# cpu.net
KiCad netlist of a schematic drawn in Altium Designer
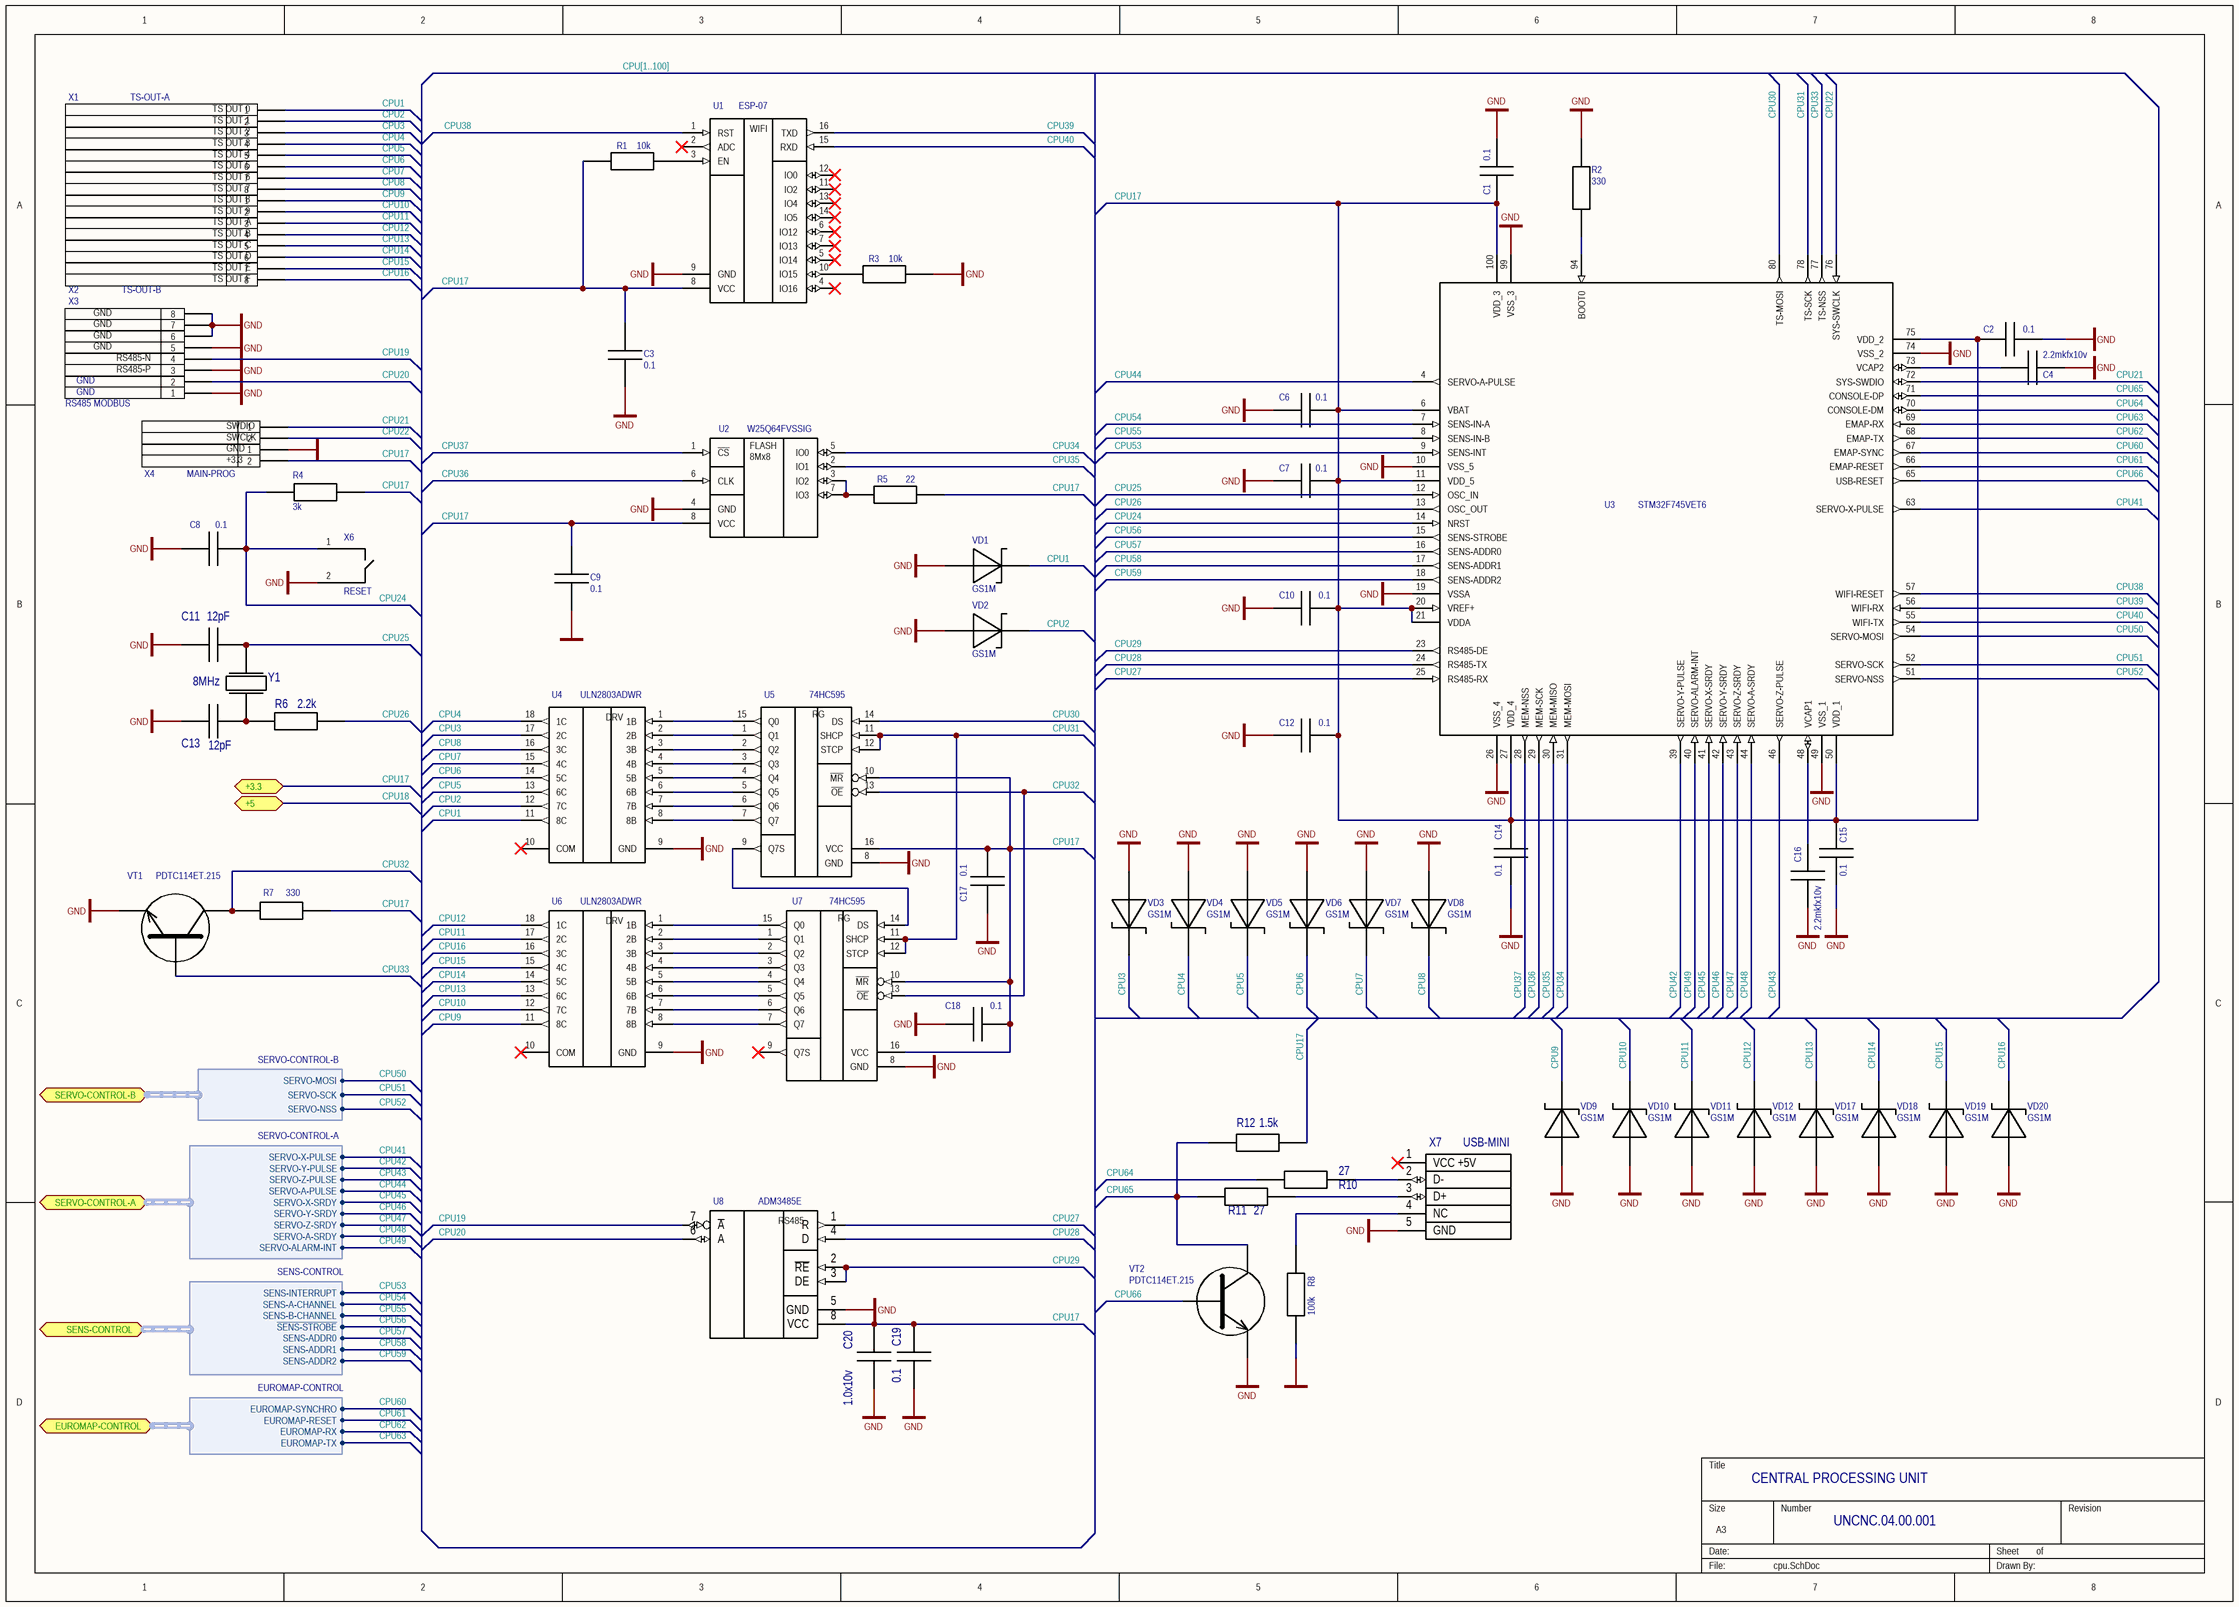
[diagram p0: cpu.SchDoc]

(export (version "E")
  (design (tool "Eeschema 10.0.6"))
  (components
    (comp (ref "C1")
      (value "0.1")
      (footprint "CAPC1608X05N")
      (description "SMD конденсатор")
      (libsource (lib "") (part "C_1"))
    )
    (comp (ref "C2")
      (value "0.1")
      (footprint "CAPC1608X05N")
      (description "SMD конденсатор")
      (libsource (lib "ulysses_library") (part "C"))
    )
    (comp (ref "C3")
      (value "0.1")
      (footprint "CAPC2012X04N")
      (description "SMD конденсатор")
      (libsource (lib "ulysses_library") (part "C"))
    )
    (comp (ref "C4")
      (value "2.2mkfx10v")
      (footprint "CAPC1608X05N")
      (description "SMD конденсатор")
      (libsource (lib "ulysses_library") (part "C"))
    )
    (comp (ref "C6")
      (value "0.1")
      (footprint "CAPC1608X05N")
      (description "SMD конденсатор")
      (libsource (lib "ulysses_library") (part "C"))
    )
    (comp (ref "C7")
      (value "0.1")
      (footprint "CAPC1608X05N")
      (description "SMD конденсатор")
      (libsource (lib "ulysses_library") (part "C"))
    )
    (comp (ref "C8")
      (value "0.1")
      (footprint "CAPC1608X05N")
      (description "SMD конденсатор")
      (libsource (lib "ulysses_library") (part "C"))
    )
    (comp (ref "C9")
      (value "0.1")
      (footprint "CAPC2012X04N")
      (description "SMD конденсатор")
      (libsource (lib "ulysses_library") (part "C"))
    )
    (comp (ref "C10")
      (value "0.1")
      (footprint "CAPC1608X05N")
      (description "SMD конденсатор")
      (libsource (lib "ulysses_library") (part "C"))
    )
    (comp (ref "C11")
      (value "12pF")
      (footprint "CAPC1608X05N")
      (description "SMD конденсатор")
      (libsource (lib "ulysses_library") (part "C"))
    )
    (comp (ref "C12")
      (value "0.1")
      (footprint "CAPC1608X05N")
      (description "SMD конденсатор")
      (libsource (lib "ulysses_library") (part "C"))
    )
    (comp (ref "C13")
      (value "12pF")
      (footprint "CAPC1608X05N")
      (description "SMD конденсатор")
      (libsource (lib "ulysses_library") (part "C"))
    )
    (comp (ref "C14")
      (value "0.1")
      (footprint "CAPC1608X05N")
      (description "SMD конденсатор")
      (libsource (lib "ulysses_library") (part "C"))
    )
    (comp (ref "C15")
      (value "0.1")
      (footprint "CAPC1608X05N")
      (description "SMD конденсатор")
      (libsource (lib "ulysses_library") (part "C"))
    )
    (comp (ref "C16")
      (value "2.2mkfx10v")
      (footprint "CAPC1608X05N")
      (description "SMD конденсатор")
      (libsource (lib "ulysses_library") (part "C"))
    )
    (comp (ref "C17")
      (value "0.1")
      (footprint "CAPC2012X04N")
      (description "SMD конденсатор")
      (libsource (lib "ulysses_library") (part "C"))
    )
    (comp (ref "C18")
      (value "0.1")
      (footprint "CAPC2012X04N")
      (description "SMD конденсатор")
      (libsource (lib "ulysses_library") (part "C"))
    )
    (comp (ref "C19")
      (value "0.1")
      (footprint "CAPC2012X04N")
      (description "SMD конденсатор")
      (libsource (lib "ulysses_library") (part "C"))
    )
    (comp (ref "C20")
      (value "1.0x10v")
      (footprint "CAPC2012X04N")
      (description "SMD конденсатор")
      (libsource (lib "ulysses_library") (part "C"))
    )
    (comp (ref "R1")
      (value "10k")
      (footprint "RESC2012X04N")
      (description "SMD резистор")
      (libsource (lib "ulysses_library") (part "R"))
    )
    (comp (ref "R2")
      (value "330")
      (footprint "RESC1608X05N")
      (description "SMD резистор")
      (libsource (lib "") (part "R_1"))
    )
    (comp (ref "R3")
      (value "10k")
      (footprint "RESC2012X04N")
      (description "SMD резистор")
      (libsource (lib "ulysses_library") (part "R"))
    )
    (comp (ref "R4")
      (value "3k")
      (footprint "RESC1608X05N")
      (description "SMD резистор")
      (libsource (lib "ulysses_library") (part "R"))
    )
    (comp (ref "R5")
      (value "22")
      (footprint "RESC2012X04N")
      (description "SMD резистор")
      (libsource (lib "ulysses_library") (part "R"))
    )
    (comp (ref "R6")
      (value "2.2k")
      (footprint "RESC1608X05N")
      (description "SMD резистор")
      (libsource (lib "ulysses_library") (part "R"))
    )
    (comp (ref "R7")
      (value "330")
      (footprint "RESC1608X05N")
      (description "SMD резистор")
      (libsource (lib "ulysses_library") (part "R"))
    )
    (comp (ref "R8")
      (value "100k")
      (footprint "RESC2012X04N")
      (description "SMD резистор")
      (libsource (lib "ulysses_library") (part "R"))
    )
    (comp (ref "R10")
      (value "27")
      (footprint "RESC2012X04N")
      (description "SMD резистор")
      (libsource (lib "ulysses_library") (part "R"))
    )
    (comp (ref "R11")
      (value "27")
      (footprint "RESC2012X04N")
      (description "SMD резистор")
      (libsource (lib "ulysses_library") (part "R"))
    )
    (comp (ref "R12")
      (value "1.5k")
      (footprint "RESC2012X04N")
      (description "SMD резистор")
      (libsource (lib "ulysses_library") (part "R"))
    )
    (comp (ref "U1")
      (value "ESP-07")
      (footprint "ESP-07")
      (description "WIFI модуль")
      (libsource (lib "ulysses_library") (part "ESP-07 Wi-Fi module"))
    )
    (comp (ref "U2")
      (value "W25Q64FVSSIG")
      (footprint "SOIC127P790X203-8N(WIDE)")
      (description "FLASH 8Mx8")
      (libsource (lib "ulysses_library") (part "W25Q64FVSSIG"))
    )
    (comp (ref "U3")
      (value "STM32F745VET6")
      (footprint "TSQFP50P1600X1600X160-100N")
      (description "ARM7 microcontroller")
      (libsource (lib "ulysses_library") (part "STM32F745VET6"))
    )
    (comp (ref "U4")
      (value "ULN2803ADWR")
      (footprint "SOIC127P1030X265-18N")
      (description "8 Darlington transistors")
      (libsource (lib "ulysses_library") (part "ULN2803ADWR"))
    )
    (comp (ref "U5")
      (value "74HC595")
      (footprint "SOP127P700X210-16N")
      (libsource (lib "ulysses_library") (part "74HC595"))
    )
    (comp (ref "U6")
      (value "ULN2803ADWR")
      (footprint "SOIC127P1030X265-18N")
      (description "8 Darlington transistors")
      (libsource (lib "ulysses_library") (part "ULN2803ADWR"))
    )
    (comp (ref "U7")
      (value "74HC595")
      (footprint "SOP127P700X210-16N")
      (libsource (lib "ulysses_library") (part "74HC595"))
    )
    (comp (ref "U8")
      (value "ADM3485E")
      (footprint "SOIC127P600X175-8N")
      (description "RS-485 line driver")
      (libsource (lib "ulysses_library") (part "SN65176BD"))
    )
    (comp (ref "VD1")
      (value "GS1M")
      (footprint "DIOM4336X21N")
      (description "диод Шоттки")
      (libsource (lib "ulysses_library") (part "SS26"))
    )
    (comp (ref "VD2")
      (value "GS1M")
      (footprint "DIOM4336X21N")
      (description "диод Шоттки")
      (libsource (lib "ulysses_library") (part "SS26"))
    )
    (comp (ref "VD3")
      (value "GS1M")
      (footprint "DIOM4336X21N")
      (description "диод Шоттки")
      (libsource (lib "ulysses_library") (part "SS26"))
    )
    (comp (ref "VD4")
      (value "GS1M")
      (footprint "DIOM4336X21N")
      (description "диод Шоттки")
      (libsource (lib "ulysses_library") (part "SS26"))
    )
    (comp (ref "VD5")
      (value "GS1M")
      (footprint "DIOM4336X21N")
      (description "диод Шоттки")
      (libsource (lib "ulysses_library") (part "SS26"))
    )
    (comp (ref "VD6")
      (value "GS1M")
      (footprint "DIOM4336X21N")
      (description "диод Шоттки")
      (libsource (lib "ulysses_library") (part "SS26"))
    )
    (comp (ref "VD7")
      (value "GS1M")
      (footprint "DIOM4336X21N")
      (description "диод Шоттки")
      (libsource (lib "ulysses_library") (part "SS26"))
    )
    (comp (ref "VD8")
      (value "GS1M")
      (footprint "DIOM4336X21N")
      (description "диод Шоттки")
      (libsource (lib "") (part "SS26_1"))
    )
    (comp (ref "VD9")
      (value "GS1M")
      (footprint "DIOM4336X21N")
      (description "диод Шоттки")
      (libsource (lib "ulysses_library") (part "SS26"))
    )
    (comp (ref "VD10")
      (value "GS1M")
      (footprint "DIOM4336X21N")
      (description "диод Шоттки")
      (libsource (lib "ulysses_library") (part "SS26"))
    )
    (comp (ref "VD11")
      (value "GS1M")
      (footprint "DIOM4336X21N")
      (description "диод Шоттки")
      (libsource (lib "ulysses_library") (part "SS26"))
    )
    (comp (ref "VD12")
      (value "GS1M")
      (footprint "DIOM4336X21N")
      (description "диод Шоттки")
      (libsource (lib "ulysses_library") (part "SS26"))
    )
    (comp (ref "VD17")
      (value "GS1M")
      (footprint "DIOM4336X21N")
      (description "диод Шоттки")
      (libsource (lib "ulysses_library") (part "SS26"))
    )
    (comp (ref "VD18")
      (value "GS1M")
      (footprint "DIOM4336X21N")
      (description "диод Шоттки")
      (libsource (lib "ulysses_library") (part "SS26"))
    )
    (comp (ref "VD19")
      (value "GS1M")
      (footprint "DIOM4336X21N")
      (description "диод Шоттки")
      (libsource (lib "ulysses_library") (part "SS26"))
    )
    (comp (ref "VD20")
      (value "GS1M")
      (footprint "DIOM4336X21N")
      (description "диод Шоттки")
      (libsource (lib "ulysses_library") (part "SS26"))
    )
    (comp (ref "VT1")
      (value "PDTC114ET.215")
      (footprint "SOT95P238X102-3N")
      (description "NPN transistor with bias circuit")
      (libsource (lib "ulysses_library") (part "PDTC114ET.215"))
    )
    (comp (ref "VT2")
      (value "PDTC114ET.215")
      (footprint "SOT95P238X102-3N")
      (description "NPN transistor with bias circuit")
      (libsource (lib "") (part "PDTC114ET.215_1"))
    )
    (comp (ref "X1")
      (value "TS-OUT-A")
      (footprint "MINI-FIT-8-WAY-SM")
      (libsource (lib "ulysses_library") (part "MINI-FIT-8-WAY-M"))
    )
    (comp (ref "X2")
      (value "TS-OUT-B")
      (footprint "MINI-FIT-8-WAY-SM")
      (libsource (lib "") (part "MINI-FIT-8-WAY-M_1"))
    )
    (comp (ref "X3")
      (value "RS485 MODBUS")
      (footprint "RJ45-CAN")
      (description "CAN-Bus connector")
      (libsource (lib "ulysses_library") (part "RJ45-CAN"))
    )
    (comp (ref "X4")
      (value "MAIN-PROG")
      (footprint "ZL201-2")
      (libsource (lib "ulysses_library") (part "Jamper ZL201"))
    )
    (comp (ref "X5")
      (value "Jamper ZL201")
      (footprint "ZL201-2")
      (libsource (lib "ulysses_library") (part "Jamper ZL201"))
    )
    (comp (ref "X6")
      (value "RESET")
      (footprint "TACT SWITCH")
      (libsource (lib "ulysses_library") (part "TACT SWITCH"))
    )
    (comp (ref "X7")
      (value "USB-MINI")
      (footprint "229-5FB-MINI-USB")
      (description "Разъем USB-B розетка")
      (libsource (lib "ulysses_library") (part "USB-MINI"))
    )
    (comp (ref "Y1")
      (value "8MHz")
      (footprint "KX-13")
      (description "Кварцевый резонатор")
      (libsource (lib "ulysses_library") (part "CERAMIC-RESONATOR"))
    )
  )
  (nets
    (net (code "40") (name "/CPU1") (class "Default")
      (node (ref "U4") (pin "11") (pinfunction "8C_11") (pintype "output"))
      (node (ref "VD1") (pin "1") (pinfunction "C_1") (pintype "passive"))
      (node (ref "X1") (pin "1") (pinfunction "1_1") (pintype "passive"))
    )
    (net (code "41") (name "/CPU2") (class "Default")
      (node (ref "U4") (pin "12") (pinfunction "7C_12") (pintype "output"))
      (node (ref "VD2") (pin "1") (pinfunction "C_1") (pintype "passive"))
      (node (ref "X1") (pin "2") (pinfunction "2_2") (pintype "passive"))
    )
    (net (code "42") (name "/CPU3") (class "Default")
      (node (ref "U4") (pin "17") (pinfunction "2C_17") (pintype "output"))
      (node (ref "VD3") (pin "1") (pinfunction "C_1") (pintype "passive"))
      (node (ref "X1") (pin "3") (pinfunction "3_3") (pintype "passive"))
    )
    (net (code "43") (name "/CPU4") (class "Default")
      (node (ref "U4") (pin "18") (pinfunction "1C_18") (pintype "output"))
      (node (ref "VD4") (pin "1") (pinfunction "C_1") (pintype "passive"))
      (node (ref "X1") (pin "4") (pinfunction "4_4") (pintype "passive"))
    )
    (net (code "44") (name "/CPU5") (class "Default")
      (node (ref "U4") (pin "13") (pinfunction "6C_13") (pintype "output"))
      (node (ref "VD5") (pin "1") (pinfunction "C_1") (pintype "passive"))
      (node (ref "X1") (pin "5") (pinfunction "5_5") (pintype "passive"))
    )
    (net (code "45") (name "/CPU6") (class "Default")
      (node (ref "U4") (pin "14") (pinfunction "5C_14") (pintype "output"))
      (node (ref "VD6") (pin "1") (pinfunction "C_1") (pintype "passive"))
      (node (ref "X1") (pin "6") (pinfunction "6_6") (pintype "passive"))
    )
    (net (code "46") (name "/CPU7") (class "Default")
      (node (ref "U4") (pin "15") (pinfunction "4C_15") (pintype "output"))
      (node (ref "VD7") (pin "1") (pinfunction "C_1") (pintype "passive"))
      (node (ref "X1") (pin "7") (pinfunction "7_7") (pintype "passive"))
    )
    (net (code "47") (name "/CPU8") (class "Default")
      (node (ref "U4") (pin "16") (pinfunction "3C_16") (pintype "output"))
      (node (ref "VD8") (pin "1") (pinfunction "C_1") (pintype "passive"))
      (node (ref "X1") (pin "8") (pinfunction "8_8") (pintype "passive"))
    )
    (net (code "48") (name "/CPU9") (class "Default")
      (node (ref "U6") (pin "11") (pinfunction "8C_11") (pintype "output"))
      (node (ref "VD9") (pin "1") (pinfunction "C_1") (pintype "passive"))
      (node (ref "X2") (pin "1") (pinfunction "1_1") (pintype "passive"))
    )
    (net (code "49") (name "/CPU10") (class "Default")
      (node (ref "U6") (pin "12") (pinfunction "7C_12") (pintype "output"))
      (node (ref "VD10") (pin "1") (pinfunction "C_1") (pintype "passive"))
      (node (ref "X2") (pin "2") (pinfunction "2_2") (pintype "passive"))
    )
    (net (code "50") (name "/CPU11") (class "Default")
      (node (ref "U6") (pin "17") (pinfunction "2C_17") (pintype "output"))
      (node (ref "VD11") (pin "1") (pinfunction "C_1") (pintype "passive"))
      (node (ref "X2") (pin "3") (pinfunction "3_3") (pintype "passive"))
    )
    (net (code "51") (name "/CPU12") (class "Default")
      (node (ref "U6") (pin "18") (pinfunction "1C_18") (pintype "output"))
      (node (ref "VD12") (pin "1") (pinfunction "C_1") (pintype "passive"))
      (node (ref "X2") (pin "4") (pinfunction "4_4") (pintype "passive"))
    )
    (net (code "52") (name "/CPU13") (class "Default")
      (node (ref "U6") (pin "13") (pinfunction "6C_13") (pintype "output"))
      (node (ref "VD17") (pin "1") (pinfunction "C_1") (pintype "passive"))
      (node (ref "X2") (pin "5") (pinfunction "5_5") (pintype "passive"))
    )
    (net (code "53") (name "/CPU14") (class "Default")
      (node (ref "U6") (pin "14") (pinfunction "5C_14") (pintype "output"))
      (node (ref "VD18") (pin "1") (pinfunction "C_1") (pintype "passive"))
      (node (ref "X2") (pin "6") (pinfunction "6_6") (pintype "passive"))
    )
    (net (code "54") (name "/CPU15") (class "Default")
      (node (ref "U6") (pin "15") (pinfunction "4C_15") (pintype "output"))
      (node (ref "VD19") (pin "1") (pinfunction "C_1") (pintype "passive"))
      (node (ref "X2") (pin "7") (pinfunction "7_7") (pintype "passive"))
    )
    (net (code "55") (name "/CPU16") (class "Default")
      (node (ref "U6") (pin "16") (pinfunction "3C_16") (pintype "output"))
      (node (ref "VD20") (pin "1") (pinfunction "C_1") (pintype "passive"))
      (node (ref "X2") (pin "8") (pinfunction "8_8") (pintype "passive"))
    )
    (net (code "56") (name "/CPU17") (class "Default")
      (node (ref "C1") (pin "1") (pinfunction "1_1") (pintype "passive"))
      (node (ref "C10") (pin "1") (pinfunction "1_1") (pintype "passive"))
      (node (ref "C12") (pin "1") (pinfunction "1_1") (pintype "passive"))
      (node (ref "C14") (pin "2") (pinfunction "2_2") (pintype "passive"))
      (node (ref "C15") (pin "2") (pinfunction "2_2") (pintype "passive"))
      (node (ref "C17") (pin "2") (pinfunction "2_2") (pintype "passive"))
      (node (ref "C18") (pin "2") (pinfunction "2_2") (pintype "passive"))
      (node (ref "C19") (pin "2") (pinfunction "2_2") (pintype "passive"))
      (node (ref "C2") (pin "2") (pinfunction "2_2") (pintype "passive"))
      (node (ref "C20") (pin "2") (pinfunction "2_2") (pintype "passive"))
      (node (ref "C3") (pin "2") (pinfunction "2_2") (pintype "passive"))
      (node (ref "C6") (pin "1") (pinfunction "1_1") (pintype "passive"))
      (node (ref "C7") (pin "1") (pinfunction "1_1") (pintype "passive"))
      (node (ref "C9") (pin "2") (pinfunction "2_2") (pintype "passive"))
      (node (ref "R1") (pin "1") (pintype "passive"))
      (node (ref "R12") (pin "2") (pinfunction "2_2") (pintype "passive"))
      (node (ref "R4") (pin "1") (pintype "passive"))
      (node (ref "R5") (pin "2") (pinfunction "2_2") (pintype "passive"))
      (node (ref "R7") (pin "1") (pintype "passive"))
      (node (ref "U1") (pin "8") (pinfunction "VCC_8") (pintype "power_in"))
      (node (ref "U2") (pin "8") (pinfunction "VCC_8") (pintype "power_in"))
      (node (ref "U3") (pin "100") (pinfunction "VDD_3_100") (pintype "power_in"))
      (node (ref "U3") (pin "11") (pinfunction "VDD_5_11") (pintype "power_in"))
      (node (ref "U3") (pin "20") (pinfunction "VREF+_20") (pintype "input"))
      (node (ref "U3") (pin "21") (pinfunction "VDDA_21") (pintype "power_in"))
      (node (ref "U3") (pin "27") (pinfunction "VDD_4_27") (pintype "power_in"))
      (node (ref "U3") (pin "50") (pinfunction "VDD_1_50") (pintype "power_in"))
      (node (ref "U3") (pin "6") (pinfunction "VBAT_6") (pintype "power_in"))
      (node (ref "U3") (pin "75") (pinfunction "VDD_2_75") (pintype "power_in"))
      (node (ref "U5") (pin "10") (pinfunction "~{MR}_10") (pintype "input"))
      (node (ref "U5") (pin "16") (pinfunction "VCC_16") (pintype "power_in"))
      (node (ref "U7") (pin "10") (pinfunction "~{MR}_10") (pintype "input"))
      (node (ref "U7") (pin "16") (pinfunction "VCC_16") (pintype "power_in"))
      (node (ref "U8") (pin "8") (pinfunction "VCC_8") (pintype "power_in"))
      (node (ref "X5") (pin "2") (pinfunction "2_2") (pintype "passive"))
    )
    (net (code "58") (name "/CPU19") (class "Default")
      (node (ref "U8") (pin "7") (pinfunction "~{A}_7") (pintype "bidirectional"))
      (node (ref "X3") (pin "4") (pinfunction "4_4") (pintype "passive"))
    )
    (net (code "59") (name "/CPU20") (class "Default")
      (node (ref "U8") (pin "6") (pinfunction "A_6") (pintype "bidirectional"))
      (node (ref "X3") (pin "2") (pinfunction "2_2") (pintype "passive"))
    )
    (net (code "60") (name "/CPU21") (class "Default")
      (node (ref "U3") (pin "72") (pinfunction "SYS-SWDIO_72") (pintype "bidirectional"))
      (node (ref "X4") (pin "1") (pinfunction "1_1") (pintype "passive"))
    )
    (net (code "61") (name "/CPU22") (class "Default")
      (node (ref "U3") (pin "76") (pinfunction "SYS-SWCLK_76") (pintype "input"))
      (node (ref "X4") (pin "2") (pinfunction "2_2") (pintype "passive"))
    )
    (net (code "62") (name "/CPU24") (class "Default")
      (node (ref "C8") (pin "1") (pinfunction "1_1") (pintype "passive"))
      (node (ref "R4") (pin "2") (pinfunction "2_2") (pintype "passive"))
      (node (ref "U3") (pin "14") (pinfunction "NRST_14") (pintype "input"))
      (node (ref "X6") (pin "1") (pinfunction "1_1") (pintype "passive"))
    )
    (net (code "63") (name "/CPU25") (class "Default")
      (node (ref "C11") (pin "2") (pinfunction "2_2") (pintype "passive"))
      (node (ref "U3") (pin "12") (pinfunction "OSC_IN_12") (pintype "input"))
      (node (ref "Y1") (pin "2") (pinfunction "2_2") (pintype "passive"))
    )
    (net (code "64") (name "/CPU26") (class "Default")
      (node (ref "R6") (pin "2") (pinfunction "2_2") (pintype "passive"))
      (node (ref "U3") (pin "13") (pinfunction "OSC_OUT_13") (pintype "output"))
    )
    (net (code "65") (name "/CPU27") (class "Default")
      (node (ref "U3") (pin "25") (pinfunction "RS485-RX_25") (pintype "input"))
      (node (ref "U8") (pin "1") (pinfunction "R_1") (pintype "output"))
    )
    (net (code "66") (name "/CPU28") (class "Default")
      (node (ref "U3") (pin "24") (pinfunction "RS485-TX_24") (pintype "output"))
      (node (ref "U8") (pin "4") (pinfunction "D_4") (pintype "input"))
    )
    (net (code "67") (name "/CPU29") (class "Default")
      (node (ref "U3") (pin "23") (pinfunction "RS485-DE_23") (pintype "output"))
      (node (ref "U8") (pin "2") (pinfunction "~{RE}_2") (pintype "input"))
      (node (ref "U8") (pin "3") (pinfunction "DE_3") (pintype "input"))
    )
    (net (code "68") (name "/CPU30") (class "Default")
      (node (ref "U3") (pin "80") (pinfunction "TS-MOSI_80") (pintype "output"))
      (node (ref "U5") (pin "14") (pinfunction "DS_14") (pintype "input"))
    )
    (net (code "69") (name "/CPU31") (class "Default")
      (node (ref "U3") (pin "78") (pinfunction "TS-SCK_78") (pintype "output"))
      (node (ref "U5") (pin "11") (pinfunction "SHCP_11") (pintype "input"))
      (node (ref "U5") (pin "12") (pinfunction "STCP_12") (pintype "input"))
      (node (ref "U7") (pin "11") (pinfunction "SHCP_11") (pintype "input"))
      (node (ref "U7") (pin "12") (pinfunction "STCP_12") (pintype "input"))
    )
    (net (code "70") (name "/CPU32") (class "Default")
      (node (ref "R7") (pin "2") (pinfunction "2_2") (pintype "passive"))
      (node (ref "U5") (pin "13") (pinfunction "~{OE}_13") (pintype "input"))
      (node (ref "U7") (pin "13") (pinfunction "~{OE}_13") (pintype "input"))
      (node (ref "VT1") (pin "3") (pinfunction "C_3") (pintype "power_in"))
    )
    (net (code "71") (name "/CPU33") (class "Default")
      (node (ref "U3") (pin "77") (pinfunction "TS-NSS_77") (pintype "output"))
      (node (ref "VT1") (pin "1") (pinfunction "B_1") (pintype "power_in"))
    )
    (net (code "72") (name "/CPU34") (class "Default")
      (node (ref "U2") (pin "5") (pinfunction "IO0_5") (pintype "bidirectional"))
      (node (ref "U3") (pin "31") (pinfunction "MEM-MOSI_31") (pintype "output"))
    )
    (net (code "73") (name "/CPU35") (class "Default")
      (node (ref "U2") (pin "2") (pinfunction "IO1_2") (pintype "bidirectional"))
      (node (ref "U3") (pin "30") (pinfunction "MEM-MISO_30") (pintype "input"))
    )
    (net (code "74") (name "/CPU36") (class "Default")
      (node (ref "U2") (pin "6") (pinfunction "CLK_6") (pintype "input"))
      (node (ref "U3") (pin "29") (pinfunction "MEM-SCK_29") (pintype "output"))
    )
    (net (code "75") (name "/CPU37") (class "Default")
      (node (ref "U2") (pin "1") (pinfunction "~{CS}_1") (pintype "input"))
      (node (ref "U3") (pin "28") (pinfunction "MEM-NSS_28") (pintype "output"))
    )
    (net (code "76") (name "/CPU38") (class "Default")
      (node (ref "U1") (pin "1") (pinfunction "RST_1") (pintype "input"))
      (node (ref "U3") (pin "57") (pinfunction "WIFI-RESET_57") (pintype "output"))
    )
    (net (code "77") (name "/CPU39") (class "Default")
      (node (ref "U1") (pin "16") (pinfunction "TXD_16") (pintype "output"))
      (node (ref "U3") (pin "56") (pinfunction "WIFI-RX_56") (pintype "input"))
    )
    (net (code "78") (name "/CPU40") (class "Default")
      (node (ref "U1") (pin "15") (pinfunction "RXD_15") (pintype "input"))
      (node (ref "U3") (pin "55") (pinfunction "WIFI-TX_55") (pintype "output"))
    )
    (net (code "79") (name "/CPU41") (class "Default")
      (node (ref "U3") (pin "63") (pinfunction "SERVO-X-PULSE_63") (pintype "output"))
    )
    (net (code "80") (name "/CPU42") (class "Default")
      (node (ref "U3") (pin "39") (pinfunction "SERVO-Y-PULSE_39") (pintype "output"))
    )
    (net (code "81") (name "/CPU43") (class "Default")
      (node (ref "U3") (pin "46") (pinfunction "SERVO-Z-PULSE_46") (pintype "output"))
    )
    (net (code "82") (name "/CPU44") (class "Default")
      (node (ref "U3") (pin "4") (pinfunction "SERVO-A-PULSE_4") (pintype "output"))
    )
    (net (code "83") (name "/CPU45") (class "Default")
      (node (ref "U3") (pin "41") (pinfunction "SERVO-X-SRDY_41") (pintype "input"))
    )
    (net (code "84") (name "/CPU46") (class "Default")
      (node (ref "U3") (pin "42") (pinfunction "SERVO-Y-SRDY_42") (pintype "input"))
    )
    (net (code "85") (name "/CPU47") (class "Default")
      (node (ref "U3") (pin "43") (pinfunction "SERVO-Z-SRDY_43") (pintype "input"))
    )
    (net (code "86") (name "/CPU48") (class "Default")
      (node (ref "U3") (pin "44") (pinfunction "SERVO-A-SRDY_44") (pintype "input"))
    )
    (net (code "87") (name "/CPU49") (class "Default")
      (node (ref "U3") (pin "40") (pinfunction "SERVO-ALARM-INT_40") (pintype "input"))
    )
    (net (code "88") (name "/CPU50") (class "Default")
      (node (ref "U3") (pin "54") (pinfunction "SERVO-MOSI_54") (pintype "output"))
    )
    (net (code "89") (name "/CPU51") (class "Default")
      (node (ref "U3") (pin "52") (pinfunction "SERVO-SCK_52") (pintype "output"))
    )
    (net (code "90") (name "/CPU52") (class "Default")
      (node (ref "U3") (pin "51") (pinfunction "SERVO-NSS_51") (pintype "output"))
    )
    (net (code "91") (name "/CPU53") (class "Default")
      (node (ref "U3") (pin "9") (pinfunction "SENS-INT_9") (pintype "input"))
    )
    (net (code "92") (name "/CPU54") (class "Default")
      (node (ref "U3") (pin "7") (pinfunction "SENS-IN-A_7") (pintype "input"))
    )
    (net (code "93") (name "/CPU55") (class "Default")
      (node (ref "U3") (pin "8") (pinfunction "SENS-IN-B_8") (pintype "input"))
    )
    (net (code "94") (name "/CPU56") (class "Default")
      (node (ref "U3") (pin "15") (pinfunction "SENS-STROBE_15") (pintype "output"))
    )
    (net (code "95") (name "/CPU57") (class "Default")
      (node (ref "U3") (pin "16") (pinfunction "SENS-ADDR0_16") (pintype "output"))
    )
    (net (code "96") (name "/CPU58") (class "Default")
      (node (ref "U3") (pin "17") (pinfunction "SENS-ADDR1_17") (pintype "output"))
    )
    (net (code "97") (name "/CPU59") (class "Default")
      (node (ref "U3") (pin "18") (pinfunction "SENS-ADDR2_18") (pintype "output"))
    )
    (net (code "98") (name "/CPU60") (class "Default")
      (node (ref "U3") (pin "67") (pinfunction "EMAP-SYNC_67") (pintype "output"))
    )
    (net (code "99") (name "/CPU61") (class "Default")
      (node (ref "U3") (pin "66") (pinfunction "EMAP-RESET_66") (pintype "output"))
    )
    (net (code "100") (name "/CPU62") (class "Default")
      (node (ref "U3") (pin "68") (pinfunction "EMAP-TX_68") (pintype "output"))
    )
    (net (code "101") (name "/CPU63") (class "Default")
      (node (ref "U3") (pin "69") (pinfunction "EMAP-RX_69") (pintype "input"))
    )
    (net (code "102") (name "/CPU64") (class "Default")
      (node (ref "R10") (pin "1") (pintype "passive"))
      (node (ref "U3") (pin "70") (pinfunction "CONSOLE-DM_70") (pintype "bidirectional"))
    )
    (net (code "103") (name "/CPU65") (class "Default")
      (node (ref "R11") (pin "1") (pintype "passive"))
      (node (ref "R12") (pin "1") (pintype "passive"))
      (node (ref "U3") (pin "71") (pinfunction "CONSOLE-DP_71") (pintype "bidirectional"))
      (node (ref "VT2") (pin "3") (pinfunction "C_3") (pintype "power_in"))
    )
    (net (code "104") (name "/CPU66") (class "Default")
      (node (ref "U3") (pin "65") (pinfunction "USB-RESET_65") (pintype "output"))
      (node (ref "VT2") (pin "1") (pinfunction "B_1") (pintype "power_in"))
    )
    (net (code "110") (name "GND") (class "Default")
      (node (ref "C1") (pin "2") (pinfunction "2_2") (pintype "passive"))
      (node (ref "C10") (pin "2") (pinfunction "2_2") (pintype "passive"))
      (node (ref "C11") (pin "1") (pinfunction "1_1") (pintype "passive"))
      (node (ref "C12") (pin "2") (pinfunction "2_2") (pintype "passive"))
      (node (ref "C13") (pin "1") (pinfunction "1_1") (pintype "passive"))
      (node (ref "C14") (pin "1") (pinfunction "1_1") (pintype "passive"))
      (node (ref "C15") (pin "1") (pinfunction "1_1") (pintype "passive"))
      (node (ref "C16") (pin "1") (pinfunction "1_1") (pintype "passive"))
      (node (ref "C17") (pin "1") (pinfunction "1_1") (pintype "passive"))
      (node (ref "C18") (pin "1") (pinfunction "1_1") (pintype "passive"))
      (node (ref "C19") (pin "1") (pinfunction "1_1") (pintype "passive"))
      (node (ref "C2") (pin "1") (pinfunction "1_1") (pintype "passive"))
      (node (ref "C20") (pin "1") (pinfunction "1_1") (pintype "passive"))
      (node (ref "C3") (pin "1") (pinfunction "1_1") (pintype "passive"))
      (node (ref "C4") (pin "1") (pinfunction "1_1") (pintype "passive"))
      (node (ref "C6") (pin "2") (pinfunction "2_2") (pintype "passive"))
      (node (ref "C7") (pin "2") (pinfunction "2_2") (pintype "passive"))
      (node (ref "C8") (pin "2") (pinfunction "2_2") (pintype "passive"))
      (node (ref "C9") (pin "1") (pinfunction "1_1") (pintype "passive"))
      (node (ref "R2") (pin "2") (pinfunction "2_2") (pintype "passive"))
      (node (ref "R3") (pin "2") (pinfunction "2_2") (pintype "passive"))
      (node (ref "R8") (pin "1") (pintype "passive"))
      (node (ref "U1") (pin "9") (pinfunction "GND_9") (pintype "power_in"))
      (node (ref "U2") (pin "4") (pinfunction "GND_4") (pintype "power_in"))
      (node (ref "U3") (pin "10") (pinfunction "VSS_5_10") (pintype "power_in"))
      (node (ref "U3") (pin "19") (pinfunction "VSSA_19") (pintype "power_in"))
      (node (ref "U3") (pin "26") (pinfunction "VSS_4_26") (pintype "power_in"))
      (node (ref "U3") (pin "49") (pinfunction "VSS_1_49") (pintype "power_in"))
      (node (ref "U3") (pin "74") (pinfunction "VSS_2_74") (pintype "power_in"))
      (node (ref "U3") (pin "99") (pinfunction "VSS_3_99") (pintype "power_in"))
      (node (ref "U4") (pin "9") (pinfunction "GND_9") (pintype "power_in"))
      (node (ref "U5") (pin "8") (pinfunction "GND_8") (pintype "power_in"))
      (node (ref "U6") (pin "9") (pinfunction "GND_9") (pintype "power_in"))
      (node (ref "U7") (pin "8") (pinfunction "GND_8") (pintype "power_in"))
      (node (ref "U8") (pin "5") (pinfunction "GND_5") (pintype "power_in"))
      (node (ref "VD1") (pin "2") (pinfunction "A_2") (pintype "passive"))
      (node (ref "VD10") (pin "2") (pinfunction "A_2") (pintype "passive"))
      (node (ref "VD11") (pin "2") (pinfunction "A_2") (pintype "passive"))
      (node (ref "VD12") (pin "2") (pinfunction "A_2") (pintype "passive"))
      (node (ref "VD17") (pin "2") (pinfunction "A_2") (pintype "passive"))
      (node (ref "VD18") (pin "2") (pinfunction "A_2") (pintype "passive"))
      (node (ref "VD19") (pin "2") (pinfunction "A_2") (pintype "passive"))
      (node (ref "VD2") (pin "2") (pinfunction "A_2") (pintype "passive"))
      (node (ref "VD20") (pin "2") (pinfunction "A_2") (pintype "passive"))
      (node (ref "VD3") (pin "2") (pinfunction "A_2") (pintype "passive"))
      (node (ref "VD4") (pin "2") (pinfunction "A_2") (pintype "passive"))
      (node (ref "VD5") (pin "2") (pinfunction "A_2") (pintype "passive"))
      (node (ref "VD6") (pin "2") (pinfunction "A_2") (pintype "passive"))
      (node (ref "VD7") (pin "2") (pinfunction "A_2") (pintype "passive"))
      (node (ref "VD8") (pin "2") (pinfunction "A_2") (pintype "passive"))
      (node (ref "VD9") (pin "2") (pinfunction "A_2") (pintype "passive"))
      (node (ref "VT1") (pin "2") (pinfunction "E_2") (pintype "power_in"))
      (node (ref "VT2") (pin "2") (pinfunction "E_2") (pintype "power_in"))
      (node (ref "X3") (pin "1") (pinfunction "1_1") (pintype "passive"))
      (node (ref "X3") (pin "3") (pinfunction "3_3") (pintype "passive"))
      (node (ref "X3") (pin "5") (pinfunction "5_5") (pintype "passive"))
      (node (ref "X3") (pin "6") (pinfunction "6_6") (pintype "passive"))
      (node (ref "X3") (pin "7") (pinfunction "7_7") (pintype "passive"))
      (node (ref "X3") (pin "8") (pinfunction "8_8") (pintype "passive"))
      (node (ref "X5") (pin "1") (pinfunction "1_1") (pintype "passive"))
      (node (ref "X6") (pin "2") (pinfunction "2_2") (pintype "passive"))
      (node (ref "X7") (pin "5") (pinfunction "GND_5") (pintype "passive"))
    )
    (net (code "111") (name "Net-(C13-Pad2)") (class "Default")
      (node (ref "C13") (pin "2") (pinfunction "2_2") (pintype "passive"))
      (node (ref "R6") (pin "1") (pintype "passive"))
      (node (ref "Y1") (pin "1") (pinfunction "1_1") (pintype "passive"))
    )
    (net (code "112") (name "Net-(U1-EN)") (class "Default")
      (node (ref "R1") (pin "2") (pinfunction "2_2") (pintype "passive"))
      (node (ref "U1") (pin "3") (pinfunction "EN_3") (pintype "input"))
    )
    (net (code "113") (name "Net-(U1-IO15)") (class "Default")
      (node (ref "R3") (pin "1") (pintype "passive"))
      (node (ref "U1") (pin "10") (pinfunction "IO15_10") (pintype "bidirectional"))
    )
    (net (code "114") (name "Net-(U2-IO2)") (class "Default")
      (node (ref "R5") (pin "1") (pintype "passive"))
      (node (ref "U2") (pin "3") (pinfunction "IO2_3") (pintype "bidirectional"))
      (node (ref "U2") (pin "7") (pinfunction "IO3_7") (pintype "bidirectional"))
    )
    (net (code "115") (name "Net-(U3-BOOT0)") (class "Default")
      (node (ref "R2") (pin "1") (pintype "passive"))
      (node (ref "U3") (pin "94") (pinfunction "BOOT0_94") (pintype "input"))
    )
    (net (code "116") (name "Net-(U3-VCAP1)") (class "Default")
      (node (ref "C16") (pin "2") (pinfunction "2_2") (pintype "passive"))
      (node (ref "U3") (pin "48") (pinfunction "VCAP1_48") (pintype "bidirectional"))
    )
    (net (code "117") (name "Net-(U3-VCAP2)") (class "Default")
      (node (ref "C4") (pin "2") (pinfunction "2_2") (pintype "passive"))
      (node (ref "U3") (pin "73") (pinfunction "VCAP2_73") (pintype "bidirectional"))
    )
    (net (code "118") (name "Net-(U4-1B)") (class "Default")
      (node (ref "U4") (pin "1") (pinfunction "1B_1") (pintype "input"))
      (node (ref "U5") (pin "15") (pinfunction "Q0_15") (pintype "output"))
    )
    (net (code "119") (name "Net-(U4-2B)") (class "Default")
      (node (ref "U4") (pin "2") (pinfunction "2B_2") (pintype "input"))
      (node (ref "U5") (pin "1") (pinfunction "Q1_1") (pintype "output"))
    )
    (net (code "120") (name "Net-(U4-3B)") (class "Default")
      (node (ref "U4") (pin "3") (pinfunction "3B_3") (pintype "input"))
      (node (ref "U5") (pin "2") (pinfunction "Q2_2") (pintype "output"))
    )
    (net (code "121") (name "Net-(U4-4B)") (class "Default")
      (node (ref "U4") (pin "4") (pinfunction "4B_4") (pintype "input"))
      (node (ref "U5") (pin "3") (pinfunction "Q3_3") (pintype "output"))
    )
    (net (code "122") (name "Net-(U4-5B)") (class "Default")
      (node (ref "U4") (pin "5") (pinfunction "5B_5") (pintype "input"))
      (node (ref "U5") (pin "4") (pinfunction "Q4_4") (pintype "output"))
    )
    (net (code "123") (name "Net-(U4-6B)") (class "Default")
      (node (ref "U4") (pin "6") (pinfunction "6B_6") (pintype "input"))
      (node (ref "U5") (pin "5") (pinfunction "Q5_5") (pintype "output"))
    )
    (net (code "124") (name "Net-(U4-7B)") (class "Default")
      (node (ref "U4") (pin "7") (pinfunction "7B_7") (pintype "input"))
      (node (ref "U5") (pin "6") (pinfunction "Q6_6") (pintype "output"))
    )
    (net (code "125") (name "Net-(U4-8B)") (class "Default")
      (node (ref "U4") (pin "8") (pinfunction "8B_8") (pintype "input"))
      (node (ref "U5") (pin "7") (pinfunction "Q7_7") (pintype "output"))
    )
    (net (code "126") (name "Net-(U5-Q7S)") (class "Default")
      (node (ref "U5") (pin "9") (pinfunction "Q7S_9") (pintype "output"))
      (node (ref "U7") (pin "14") (pinfunction "DS_14") (pintype "input"))
    )
    (net (code "127") (name "Net-(U6-1B)") (class "Default")
      (node (ref "U6") (pin "1") (pinfunction "1B_1") (pintype "input"))
      (node (ref "U7") (pin "15") (pinfunction "Q0_15") (pintype "output"))
    )
    (net (code "128") (name "Net-(U6-2B)") (class "Default")
      (node (ref "U6") (pin "2") (pinfunction "2B_2") (pintype "input"))
      (node (ref "U7") (pin "1") (pinfunction "Q1_1") (pintype "output"))
    )
    (net (code "129") (name "Net-(U6-3B)") (class "Default")
      (node (ref "U6") (pin "3") (pinfunction "3B_3") (pintype "input"))
      (node (ref "U7") (pin "2") (pinfunction "Q2_2") (pintype "output"))
    )
    (net (code "130") (name "Net-(U6-4B)") (class "Default")
      (node (ref "U6") (pin "4") (pinfunction "4B_4") (pintype "input"))
      (node (ref "U7") (pin "3") (pinfunction "Q3_3") (pintype "output"))
    )
    (net (code "131") (name "Net-(U6-5B)") (class "Default")
      (node (ref "U6") (pin "5") (pinfunction "5B_5") (pintype "input"))
      (node (ref "U7") (pin "4") (pinfunction "Q4_4") (pintype "output"))
    )
    (net (code "132") (name "Net-(U6-6B)") (class "Default")
      (node (ref "U6") (pin "6") (pinfunction "6B_6") (pintype "input"))
      (node (ref "U7") (pin "5") (pinfunction "Q5_5") (pintype "output"))
    )
    (net (code "133") (name "Net-(U6-7B)") (class "Default")
      (node (ref "U6") (pin "7") (pinfunction "7B_7") (pintype "input"))
      (node (ref "U7") (pin "6") (pinfunction "Q6_6") (pintype "output"))
    )
    (net (code "134") (name "Net-(U6-8B)") (class "Default")
      (node (ref "U6") (pin "8") (pinfunction "8B_8") (pintype "input"))
      (node (ref "U7") (pin "7") (pinfunction "Q7_7") (pintype "output"))
    )
    (net (code "135") (name "Net-(X7-D+)") (class "Default")
      (node (ref "R11") (pin "2") (pinfunction "2_2") (pintype "passive"))
      (node (ref "X7") (pin "3") (pinfunction "D+_3") (pintype "bidirectional"))
    )
    (net (code "136") (name "Net-(X7-D-)") (class "Default")
      (node (ref "R10") (pin "2") (pinfunction "2_2") (pintype "passive"))
      (node (ref "X7") (pin "2") (pinfunction "D-_2") (pintype "bidirectional"))
    )
    (net (code "137") (name "Net-(X7-NC)") (class "Default")
      (node (ref "R8") (pin "2") (pinfunction "2_2") (pintype "passive"))
      (node (ref "X7") (pin "4") (pinfunction "NC_4") (pintype "power_in"))
    )
    (net (code "138") (name "unconnected-(U1-ADC-Pad2)") (class "Default")
      (node (ref "U1") (pin "2") (pinfunction "ADC_2") (pintype "output+no_connect"))
    )
    (net (code "139") (name "unconnected-(U1-IO0-Pad12)") (class "Default")
      (node (ref "U1") (pin "12") (pinfunction "IO0_12") (pintype "bidirectional+no_connect"))
    )
    (net (code "140") (name "unconnected-(U1-IO2-Pad11)") (class "Default")
      (node (ref "U1") (pin "11") (pinfunction "IO2_11") (pintype "bidirectional+no_connect"))
    )
    (net (code "141") (name "unconnected-(U1-IO4-Pad13)") (class "Default")
      (node (ref "U1") (pin "13") (pinfunction "IO4_13") (pintype "bidirectional+no_connect"))
    )
    (net (code "142") (name "unconnected-(U1-IO5-Pad14)") (class "Default")
      (node (ref "U1") (pin "14") (pinfunction "IO5_14") (pintype "bidirectional+no_connect"))
    )
    (net (code "143") (name "unconnected-(U1-IO12-Pad6)") (class "Default")
      (node (ref "U1") (pin "6") (pinfunction "IO12_6") (pintype "bidirectional+no_connect"))
    )
    (net (code "144") (name "unconnected-(U1-IO13-Pad7)") (class "Default")
      (node (ref "U1") (pin "7") (pinfunction "IO13_7") (pintype "bidirectional+no_connect"))
    )
    (net (code "145") (name "unconnected-(U1-IO14-Pad5)") (class "Default")
      (node (ref "U1") (pin "5") (pinfunction "IO14_5") (pintype "bidirectional+no_connect"))
    )
    (net (code "146") (name "unconnected-(U1-IO16-Pad4)") (class "Default")
      (node (ref "U1") (pin "4") (pinfunction "IO16_4") (pintype "bidirectional+no_connect"))
    )
    (net (code "147") (name "unconnected-(U3-PA0-WKUP-Pad22)") (class "Default")
      (node (ref "U3") (pin "22") (pinfunction "PA0-WKUP_22") (pintype "input"))
    )
    (net (code "148") (name "unconnected-(U3-PB0-Pad34)") (class "Default")
      (node (ref "U3") (pin "34") (pinfunction "PB0_34") (pintype "bidirectional"))
    )
    (net (code "149") (name "unconnected-(U3-PB1-Pad35)") (class "Default")
      (node (ref "U3") (pin "35") (pinfunction "PB1_35") (pintype "bidirectional"))
    )
    (net (code "150") (name "unconnected-(U3-PB2-Pad36)") (class "Default")
      (node (ref "U3") (pin "36") (pinfunction "PB2_36") (pintype "bidirectional"))
    )
    (net (code "151") (name "unconnected-(U3-PB3-Pad89)") (class "Default")
      (node (ref "U3") (pin "89") (pinfunction "PB3_89") (pintype "bidirectional"))
    )
    (net (code "152") (name "unconnected-(U3-PB4-Pad90)") (class "Default")
      (node (ref "U3") (pin "90") (pinfunction "PB4_90") (pintype "bidirectional"))
    )
    (net (code "153") (name "unconnected-(U3-PB5-Pad91)") (class "Default")
      (node (ref "U3") (pin "91") (pinfunction "PB5_91") (pintype "bidirectional"))
    )
    (net (code "154") (name "unconnected-(U3-PB6-Pad92)") (class "Default")
      (node (ref "U3") (pin "92") (pinfunction "PB6_92") (pintype "bidirectional"))
    )
    (net (code "155") (name "unconnected-(U3-PB7-Pad93)") (class "Default")
      (node (ref "U3") (pin "93") (pinfunction "PB7_93") (pintype "bidirectional"))
    )
    (net (code "156") (name "unconnected-(U3-PB8-Pad95)") (class "Default")
      (node (ref "U3") (pin "95") (pinfunction "PB8_95") (pintype "bidirectional"))
    )
    (net (code "157") (name "unconnected-(U3-PB9-Pad96)") (class "Default")
      (node (ref "U3") (pin "96") (pinfunction "PB9_96") (pintype "bidirectional"))
    )
    (net (code "158") (name "unconnected-(U3-PB11-Pad47)") (class "Default")
      (node (ref "U3") (pin "47") (pinfunction "PB11_47") (pintype "bidirectional"))
    )
    (net (code "159") (name "unconnected-(U3-PB14-Pad53)") (class "Default")
      (node (ref "U3") (pin "53") (pinfunction "PB14_53") (pintype "bidirectional"))
    )
    (net (code "160") (name "unconnected-(U3-PC4-Pad32)") (class "Default")
      (node (ref "U3") (pin "32") (pinfunction "PC4_32") (pintype "bidirectional"))
    )
    (net (code "161") (name "unconnected-(U3-PC5-Pad33)") (class "Default")
      (node (ref "U3") (pin "33") (pinfunction "PC5_33") (pintype "bidirectional"))
    )
    (net (code "162") (name "unconnected-(U3-PC7-Pad64)") (class "Default")
      (node (ref "U3") (pin "64") (pinfunction "PC7_64") (pintype "bidirectional"))
    )
    (net (code "163") (name "unconnected-(U3-PC11-Pad79)") (class "Default")
      (node (ref "U3") (pin "79") (pinfunction "PC11_79") (pintype "bidirectional"))
    )
    (net (code "164") (name "unconnected-(U3-PD0-Pad81)") (class "Default")
      (node (ref "U3") (pin "81") (pinfunction "PD0_81") (pintype "bidirectional"))
    )
    (net (code "165") (name "unconnected-(U3-PD1-Pad82)") (class "Default")
      (node (ref "U3") (pin "82") (pinfunction "PD1_82") (pintype "bidirectional"))
    )
    (net (code "166") (name "unconnected-(U3-PD2-Pad83)") (class "Default")
      (node (ref "U3") (pin "83") (pinfunction "PD2_83") (pintype "bidirectional"))
    )
    (net (code "167") (name "unconnected-(U3-PD3-Pad84)") (class "Default")
      (node (ref "U3") (pin "84") (pinfunction "PD3_84") (pintype "bidirectional"))
    )
    (net (code "168") (name "unconnected-(U3-PD4-Pad85)") (class "Default")
      (node (ref "U3") (pin "85") (pinfunction "PD4_85") (pintype "bidirectional"))
    )
    (net (code "169") (name "unconnected-(U3-PD5-Pad86)") (class "Default")
      (node (ref "U3") (pin "86") (pinfunction "PD5_86") (pintype "bidirectional"))
    )
    (net (code "170") (name "unconnected-(U3-PD6-Pad87)") (class "Default")
      (node (ref "U3") (pin "87") (pinfunction "PD6_87") (pintype "bidirectional"))
    )
    (net (code "171") (name "unconnected-(U3-PD7-Pad88)") (class "Default")
      (node (ref "U3") (pin "88") (pinfunction "PD7_88") (pintype "bidirectional"))
    )
    (net (code "172") (name "unconnected-(U3-PD11-Pad58)") (class "Default")
      (node (ref "U3") (pin "58") (pinfunction "PD11_58") (pintype "bidirectional"))
    )
    (net (code "173") (name "unconnected-(U3-PD12-Pad59)") (class "Default")
      (node (ref "U3") (pin "59") (pinfunction "PD12_59") (pintype "bidirectional"))
    )
    (net (code "174") (name "unconnected-(U3-PD13-Pad60)") (class "Default")
      (node (ref "U3") (pin "60") (pinfunction "PD13_60") (pintype "bidirectional"))
    )
    (net (code "175") (name "unconnected-(U3-PD14-Pad61)") (class "Default")
      (node (ref "U3") (pin "61") (pinfunction "PD14_61") (pintype "bidirectional"))
    )
    (net (code "176") (name "unconnected-(U3-PD15-Pad62)") (class "Default")
      (node (ref "U3") (pin "62") (pinfunction "PD15_62") (pintype "bidirectional"))
    )
    (net (code "177") (name "unconnected-(U3-PE0-Pad97)") (class "Default")
      (node (ref "U3") (pin "97") (pinfunction "PE0_97") (pintype "bidirectional"))
    )
    (net (code "178") (name "unconnected-(U3-PE1-Pad98)") (class "Default")
      (node (ref "U3") (pin "98") (pinfunction "PE1_98") (pintype "bidirectional"))
    )
    (net (code "179") (name "unconnected-(U3-PE2-Pad1)") (class "Default")
      (node (ref "U3") (pin "1") (pinfunction "PE2_1") (pintype "bidirectional"))
    )
    (net (code "180") (name "unconnected-(U3-PE3-Pad2)") (class "Default")
      (node (ref "U3") (pin "2") (pinfunction "PE3_2") (pintype "bidirectional"))
    )
    (net (code "181") (name "unconnected-(U3-PE4-Pad3)") (class "Default")
      (node (ref "U3") (pin "3") (pinfunction "PE4_3") (pintype "passive"))
    )
    (net (code "182") (name "unconnected-(U3-PE6-Pad5)") (class "Default")
      (node (ref "U3") (pin "5") (pinfunction "PE6_5") (pintype "bidirectional"))
    )
    (net (code "183") (name "unconnected-(U3-PE7-Pad37)") (class "Default")
      (node (ref "U3") (pin "37") (pinfunction "PE7_37") (pintype "bidirectional"))
    )
    (net (code "184") (name "unconnected-(U3-PE8-Pad38)") (class "Default")
      (node (ref "U3") (pin "38") (pinfunction "PE8_38") (pintype "bidirectional"))
    )
    (net (code "185") (name "unconnected-(U3-PE15-Pad45)") (class "Default")
      (node (ref "U3") (pin "45") (pinfunction "PE15_45") (pintype "bidirectional"))
    )
    (net (code "186") (name "unconnected-(U4-COM-Pad10)") (class "Default")
      (node (ref "U4") (pin "10") (pinfunction "COM_10") (pintype "power_in+no_connect"))
    )
    (net (code "187") (name "unconnected-(U6-COM-Pad10)") (class "Default")
      (node (ref "U6") (pin "10") (pinfunction "COM_10") (pintype "power_in+no_connect"))
    )
    (net (code "188") (name "unconnected-(U7-Q7S-Pad9)") (class "Default")
      (node (ref "U7") (pin "9") (pinfunction "Q7S_9") (pintype "output+no_connect"))
    )
    (net (code "189") (name "unconnected-(X7-VCC_+5V-Pad1)") (class "Default")
      (node (ref "X7") (pin "1") (pinfunction "VCC_+5V_1") (pintype "power_in+no_connect"))
    )
  )
)
